# Mainboard-v18.net
KiCad netlist of a schematic drawn in EAGLE
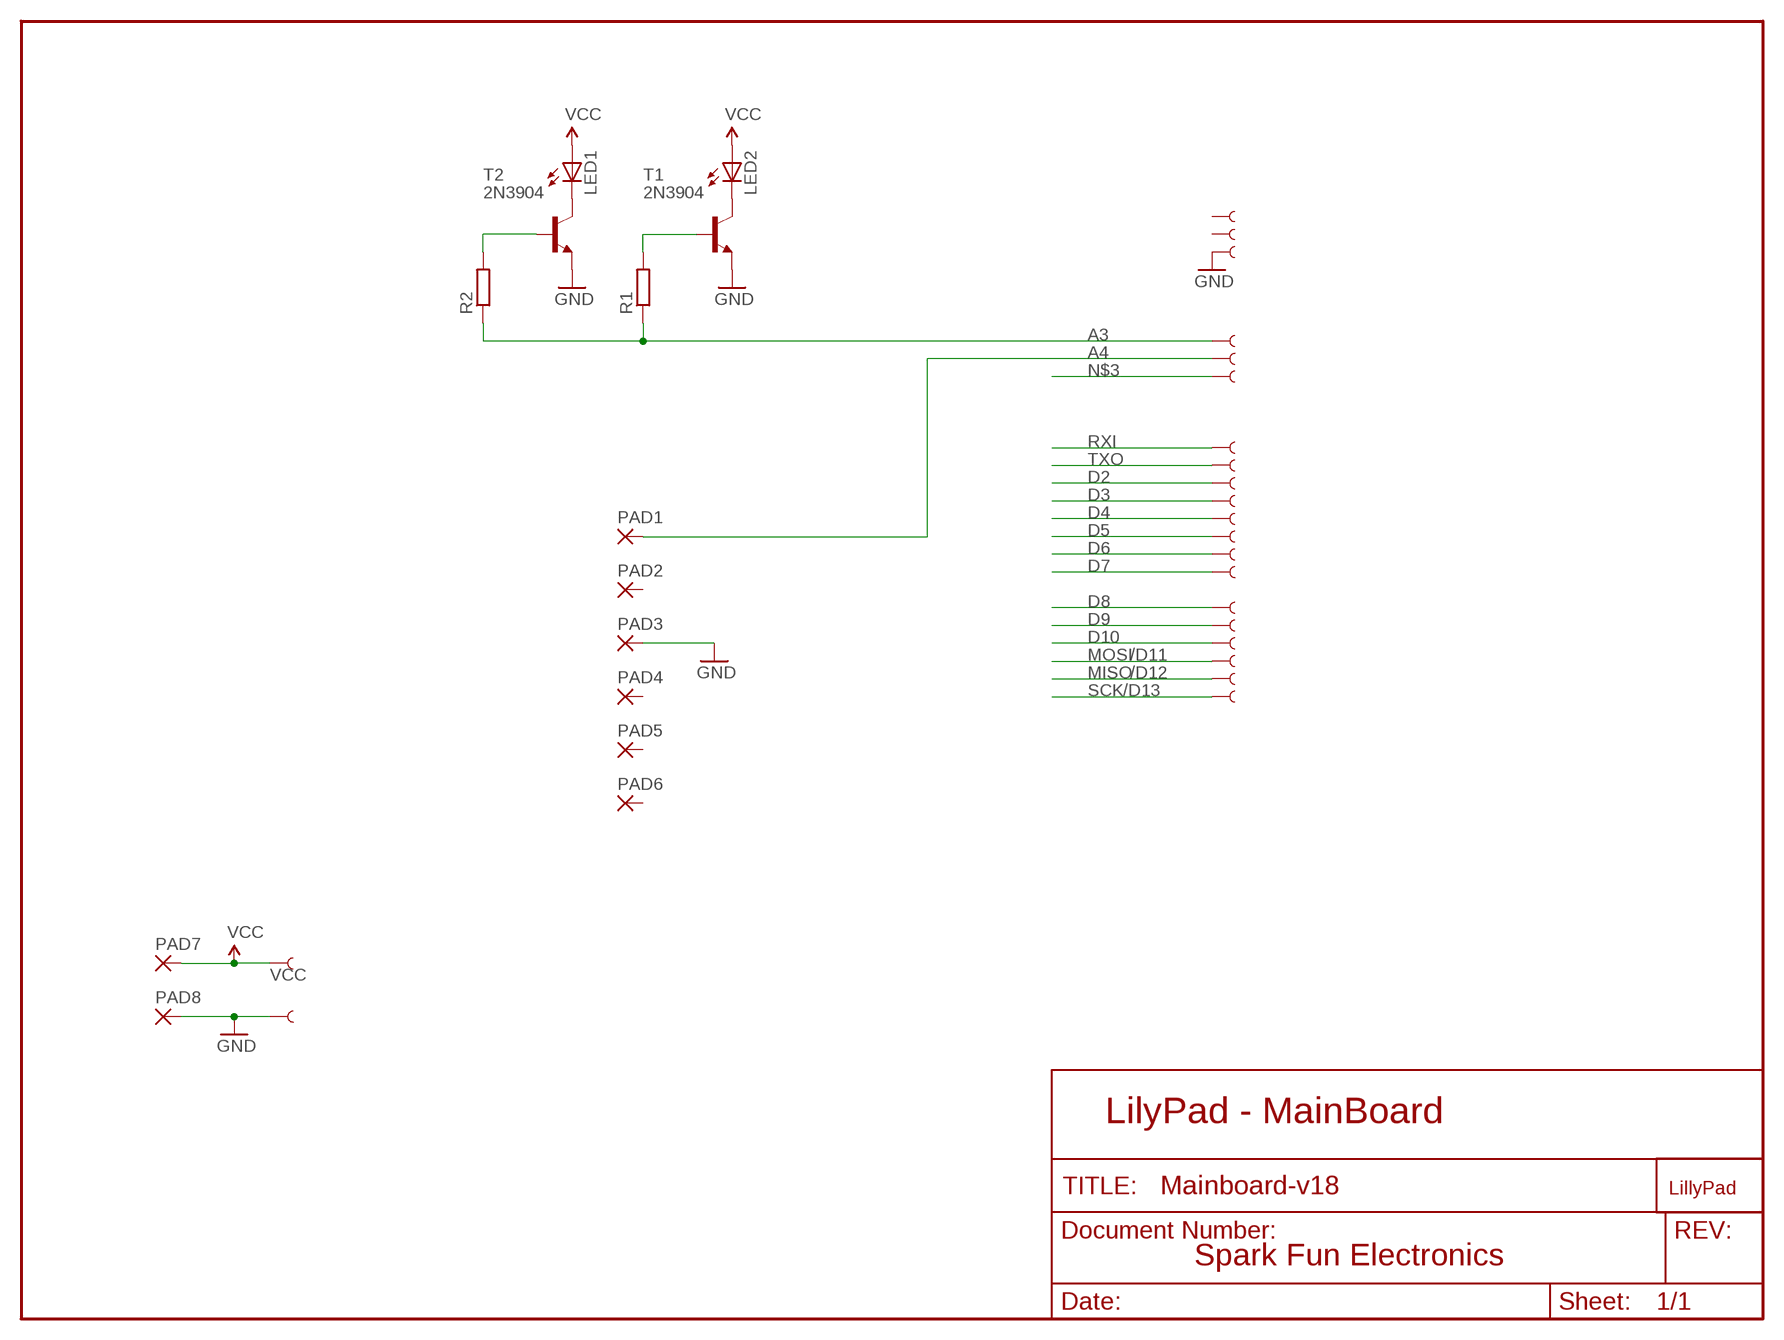
[diagram p0: schematic, sheet 1]

(export (version "E")
  (design (tool "Eeschema 10.0.6"))
  (components
    (comp (ref "GND")
      (value "SEWTAP1")
      (footprint "eagle-import:SEWTAP")
      (libsource (lib "eagle-import") (part "SEWTAP1"))
    )
    (comp (ref "LED1")
      (value "LED5MM")
      (footprint "eagle-import:LED5MM")
      (libsource (lib "eagle-import") (part "LED5MM"))
    )
    (comp (ref "LED2")
      (value "LED5MM")
      (footprint "eagle-import:LED5MM")
      (libsource (lib "eagle-import") (part "LED5MM"))
    )
    (comp (ref "PAD1")
      (value "1,6/0,8")
      (footprint "eagle-import:1,6_0,8")
      (libsource (lib "eagle-import") (part "1,6/0,8"))
    )
    (comp (ref "PAD2")
      (value "1,6/0,8")
      (footprint "eagle-import:1,6_0,8")
      (libsource (lib "eagle-import") (part "1,6/0,8"))
    )
    (comp (ref "PAD3")
      (value "1,6/0,8")
      (footprint "eagle-import:1,6_0,8")
      (libsource (lib "eagle-import") (part "1,6/0,8"))
    )
    (comp (ref "PAD4")
      (value "1,6/0,8")
      (footprint "eagle-import:1,6_0,8")
      (libsource (lib "eagle-import") (part "1,6/0,8"))
    )
    (comp (ref "PAD5")
      (value "1,6/0,8")
      (footprint "eagle-import:1,6_0,8")
      (libsource (lib "eagle-import") (part "1,6/0,8"))
    )
    (comp (ref "PAD6")
      (value "1,6/0,8")
      (footprint "eagle-import:1,6_0,8")
      (libsource (lib "eagle-import") (part "1,6/0,8"))
    )
    (comp (ref "PAD7")
      (value "1,6/0,8")
      (footprint "eagle-import:1,6_0,8")
      (libsource (lib "eagle-import") (part "1,6/0,8"))
    )
    (comp (ref "PAD8")
      (value "1,6/0,8")
      (footprint "eagle-import:1,6_0,8")
      (libsource (lib "eagle-import") (part "1,6/0,8"))
    )
    (comp (ref "R1")
      (value "R-EU_0204/5")
      (footprint "eagle-import:0204_5")
      (libsource (lib "eagle-import") (part "R-EU_0204/5"))
    )
    (comp (ref "R2")
      (value "R-EU_0204/5")
      (footprint "eagle-import:0204_5")
      (libsource (lib "eagle-import") (part "R-EU_0204/5"))
    )
    (comp (ref "T1")
      (value "2N3904")
      (footprint "eagle-import:TO92")
      (libsource (lib "eagle-import") (part "2N3904"))
    )
    (comp (ref "T2")
      (value "2N3904")
      (footprint "eagle-import:TO92")
      (libsource (lib "eagle-import") (part "2N3904"))
    )
    (comp (ref "U$1")
      (value "LOGO-LPLPA")
      (footprint "eagle-import:LOGO-LPA")
      (libsource (lib "eagle-import") (part "LOGO-LPLPA"))
    )
    (comp (ref "U$4")
      (value "SEWTAP1")
      (footprint "eagle-import:SEWTAP")
      (libsource (lib "eagle-import") (part "SEWTAP1"))
    )
    (comp (ref "U$30")
      (value "SEWTAP1")
      (footprint "eagle-import:SEWTAP")
      (libsource (lib "eagle-import") (part "SEWTAP1"))
    )
    (comp (ref "U$31")
      (value "SEWTAP1")
      (footprint "eagle-import:SEWTAP")
      (libsource (lib "eagle-import") (part "SEWTAP1"))
    )
    (comp (ref "U$32")
      (value "SEWTAP1")
      (footprint "eagle-import:SEWTAP")
      (libsource (lib "eagle-import") (part "SEWTAP1"))
    )
    (comp (ref "U$33")
      (value "SEWTAP1")
      (footprint "eagle-import:SEWTAP")
      (libsource (lib "eagle-import") (part "SEWTAP1"))
    )
    (comp (ref "U$34")
      (value "SEWTAP1")
      (footprint "eagle-import:SEWTAP")
      (libsource (lib "eagle-import") (part "SEWTAP1"))
    )
    (comp (ref "U$35")
      (value "SEWTAP1")
      (footprint "eagle-import:SEWTAP")
      (libsource (lib "eagle-import") (part "SEWTAP1"))
    )
    (comp (ref "U$36")
      (value "SEWTAP1")
      (footprint "eagle-import:SEWTAP")
      (libsource (lib "eagle-import") (part "SEWTAP1"))
    )
    (comp (ref "U$37")
      (value "SEWTAP1")
      (footprint "eagle-import:SEWTAP")
      (libsource (lib "eagle-import") (part "SEWTAP1"))
    )
    (comp (ref "U$38")
      (value "SEWTAP1")
      (footprint "eagle-import:SEWTAP")
      (libsource (lib "eagle-import") (part "SEWTAP1"))
    )
    (comp (ref "U$39")
      (value "SEWTAP1")
      (footprint "eagle-import:SEWTAP")
      (libsource (lib "eagle-import") (part "SEWTAP1"))
    )
    (comp (ref "U$40")
      (value "SEWTAP1")
      (footprint "eagle-import:SEWTAP")
      (libsource (lib "eagle-import") (part "SEWTAP1"))
    )
    (comp (ref "U$41")
      (value "SEWTAP1")
      (footprint "eagle-import:SEWTAP")
      (libsource (lib "eagle-import") (part "SEWTAP1"))
    )
    (comp (ref "U$42")
      (value "SEWTAP1")
      (footprint "eagle-import:SEWTAP")
      (libsource (lib "eagle-import") (part "SEWTAP1"))
    )
    (comp (ref "U$43")
      (value "SEWTAP1")
      (footprint "eagle-import:SEWTAP")
      (libsource (lib "eagle-import") (part "SEWTAP1"))
    )
    (comp (ref "U$44")
      (value "SEWTAP1")
      (footprint "eagle-import:SEWTAP")
      (libsource (lib "eagle-import") (part "SEWTAP1"))
    )
    (comp (ref "U$45")
      (value "SEWTAP1")
      (footprint "eagle-import:SEWTAP")
      (libsource (lib "eagle-import") (part "SEWTAP1"))
    )
    (comp (ref "U$46")
      (value "SEWTAP1")
      (footprint "eagle-import:SEWTAP")
      (libsource (lib "eagle-import") (part "SEWTAP1"))
    )
    (comp (ref "U$47")
      (value "SEWTAP1")
      (footprint "eagle-import:SEWTAP")
      (libsource (lib "eagle-import") (part "SEWTAP1"))
    )
    (comp (ref "U$48")
      (value "SEWTAP1")
      (footprint "eagle-import:SEWTAP")
      (libsource (lib "eagle-import") (part "SEWTAP1"))
    )
    (comp (ref "U$51")
      (value "SEWTAP1")
      (footprint "eagle-import:SEWTAP")
      (libsource (lib "eagle-import") (part "SEWTAP1"))
    )
  )
  (nets
    (net (code "1") (name "/A3") (class "Default")
      (node (ref "R1") (pin "1") (pinfunction "1_1") (pintype "passive"))
      (node (ref "R2") (pin "1") (pinfunction "1_1") (pintype "passive"))
      (node (ref "U$32") (pin "1") (pinfunction "1_1") (pintype "bidirectional"))
    )
    (net (code "2") (name "/A4") (class "Default")
      (node (ref "PAD1") (pin "1") (pinfunction "P_1") (pintype "passive"))
      (node (ref "U$33") (pin "1") (pinfunction "1_1") (pintype "bidirectional"))
    )
    (net (code "3") (name "/D2") (class "Default")
      (node (ref "U$45") (pin "1") (pinfunction "1_1") (pintype "bidirectional"))
    )
    (net (code "4") (name "/D3") (class "Default")
      (node (ref "U$44") (pin "1") (pinfunction "1_1") (pintype "bidirectional"))
    )
    (net (code "5") (name "/D4") (class "Default")
      (node (ref "U$43") (pin "1") (pinfunction "1_1") (pintype "bidirectional"))
    )
    (net (code "6") (name "/D5") (class "Default")
      (node (ref "U$42") (pin "1") (pinfunction "1_1") (pintype "bidirectional"))
    )
    (net (code "7") (name "/D6") (class "Default")
      (node (ref "U$41") (pin "1") (pinfunction "1_1") (pintype "bidirectional"))
    )
    (net (code "8") (name "/D7") (class "Default")
      (node (ref "U$48") (pin "1") (pinfunction "1_1") (pintype "bidirectional"))
    )
    (net (code "9") (name "/D8") (class "Default")
      (node (ref "U$35") (pin "1") (pinfunction "1_1") (pintype "bidirectional"))
    )
    (net (code "10") (name "/D9") (class "Default")
      (node (ref "U$36") (pin "1") (pinfunction "1_1") (pintype "bidirectional"))
    )
    (net (code "11") (name "/D10") (class "Default")
      (node (ref "U$37") (pin "1") (pinfunction "1_1") (pintype "bidirectional"))
    )
    (net (code "12") (name "/MISO") (class "Default")
      (node (ref "U$39") (pin "1") (pinfunction "1_1") (pintype "bidirectional"))
    )
    (net (code "13") (name "/MOSI") (class "Default")
      (node (ref "U$38") (pin "1") (pinfunction "1_1") (pintype "bidirectional"))
    )
    (net (code "14") (name "/N$3") (class "Default")
      (node (ref "U$34") (pin "1") (pinfunction "1_1") (pintype "bidirectional"))
    )
    (net (code "15") (name "/RXI") (class "Default")
      (node (ref "U$47") (pin "1") (pinfunction "1_1") (pintype "bidirectional"))
    )
    (net (code "16") (name "/SCK") (class "Default")
      (node (ref "U$40") (pin "1") (pinfunction "1_1") (pintype "bidirectional"))
    )
    (net (code "17") (name "/TXO") (class "Default")
      (node (ref "U$46") (pin "1") (pinfunction "1_1") (pintype "bidirectional"))
    )
    (net (code "18") (name "GND") (class "Default")
      (node (ref "PAD3") (pin "1") (pinfunction "P_1") (pintype "passive"))
      (node (ref "PAD8") (pin "1") (pinfunction "P_1") (pintype "passive"))
      (node (ref "T1") (pin "3") (pinfunction "E_3") (pintype "passive"))
      (node (ref "T2") (pin "3") (pinfunction "E_3") (pintype "passive"))
      (node (ref "U$30") (pin "1") (pinfunction "1_1") (pintype "bidirectional"))
      (node (ref "U$31") (pin "1") (pinfunction "1_1") (pintype "bidirectional"))
    )
    (net (code "19") (name "Net-(LED1-C)") (class "Default")
      (node (ref "LED1") (pin "K") (pinfunction "C_K") (pintype "passive"))
      (node (ref "T2") (pin "1") (pinfunction "C_1") (pintype "passive"))
    )
    (net (code "20") (name "Net-(LED2-C)") (class "Default")
      (node (ref "LED2") (pin "K") (pinfunction "C_K") (pintype "passive"))
      (node (ref "T1") (pin "1") (pinfunction "C_1") (pintype "passive"))
    )
    (net (code "21") (name "Net-(T1-B)") (class "Default")
      (node (ref "R1") (pin "2") (pinfunction "2_2") (pintype "passive"))
      (node (ref "T1") (pin "2") (pinfunction "B_2") (pintype "passive"))
    )
    (net (code "22") (name "Net-(T2-B)") (class "Default")
      (node (ref "R2") (pin "2") (pinfunction "2_2") (pintype "passive"))
      (node (ref "T2") (pin "2") (pinfunction "B_2") (pintype "passive"))
    )
    (net (code "23") (name "VCC") (class "Default")
      (node (ref "LED1") (pin "A") (pinfunction "A_A") (pintype "passive"))
      (node (ref "LED2") (pin "A") (pinfunction "A_A") (pintype "passive"))
      (node (ref "PAD7") (pin "1") (pinfunction "P_1") (pintype "passive"))
      (node (ref "U$4") (pin "1") (pinfunction "1_1") (pintype "bidirectional"))
    )
    (net (code "24") (name "unconnected-(GND-Pad1)") (class "Default")
      (node (ref "GND") (pin "1") (pinfunction "1_1") (pintype "bidirectional"))
    )
    (net (code "25") (name "unconnected-(PAD2-P-Pad1)") (class "Default")
      (node (ref "PAD2") (pin "1") (pinfunction "P_1") (pintype "passive"))
    )
    (net (code "26") (name "unconnected-(PAD4-P-Pad1)") (class "Default")
      (node (ref "PAD4") (pin "1") (pinfunction "P_1") (pintype "passive"))
    )
    (net (code "27") (name "unconnected-(PAD5-P-Pad1)") (class "Default")
      (node (ref "PAD5") (pin "1") (pinfunction "P_1") (pintype "passive"))
    )
    (net (code "28") (name "unconnected-(PAD6-P-Pad1)") (class "Default")
      (node (ref "PAD6") (pin "1") (pinfunction "P_1") (pintype "passive"))
    )
    (net (code "29") (name "unconnected-(U$51-Pad1)") (class "Default")
      (node (ref "U$51") (pin "1") (pinfunction "1_1") (pintype "bidirectional"))
    )
  )
)
